# DW08B.net
KiCad netlist of a schematic drawn in EAGLE
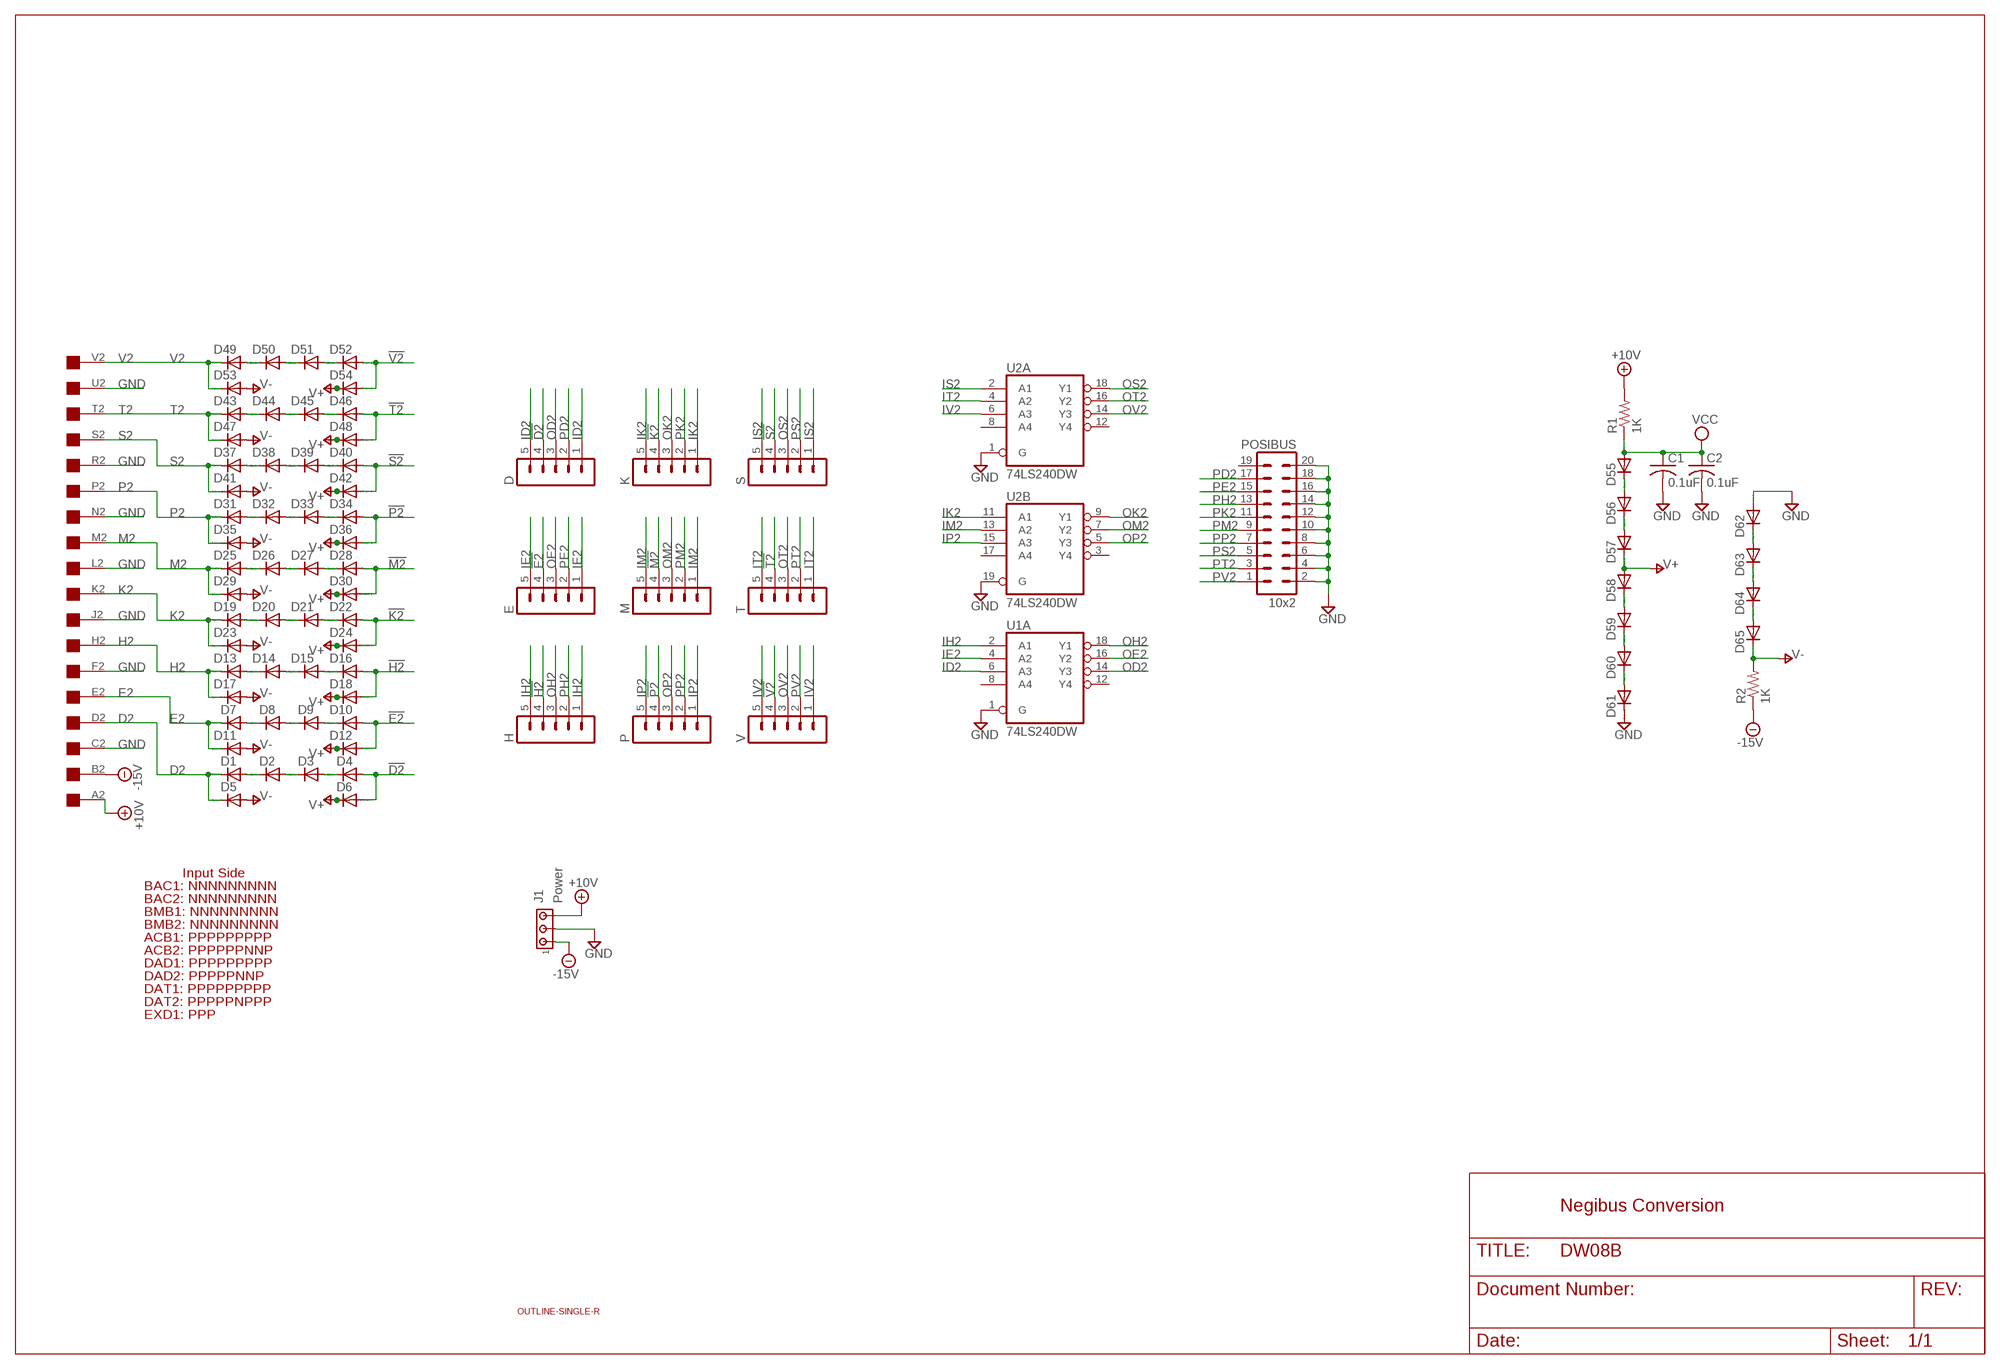
[diagram p0: schematic, sheet 1]

(export (version "E")
  (design (tool "Eeschema 10.0.6"))
  (components
    (comp (ref "C1")
      (value "0.1uF")
      (footprint "eagle-import:C050-025X075")
      (libsource (lib "eagle-import") (part "C-US050-025X075"))
    )
    (comp (ref "C2")
      (value "0.1uF")
      (footprint "eagle-import:C050-025X075")
      (libsource (lib "eagle-import") (part "C-US050-025X075"))
    )
    (comp (ref "D")
      (value "MA05-1")
      (footprint "eagle-import:MA05-1")
      (libsource (lib "eagle-import") (part "MA05-1"))
    )
    (comp (ref "D1")
      (value "1N4148WS")
      (footprint "eagle-import:SOD323-W")
      (libsource (lib "eagle-import") (part "DIODE-SOD323-W"))
    )
    (comp (ref "D2")
      (value "1N4148WS")
      (footprint "eagle-import:SOD323-W")
      (libsource (lib "eagle-import") (part "DIODE-SOD323-W"))
    )
    (comp (ref "D3")
      (value "1N4148WS")
      (footprint "eagle-import:SOD323-W")
      (libsource (lib "eagle-import") (part "DIODE-SOD323-W"))
    )
    (comp (ref "D4")
      (value "1N4148WS")
      (footprint "eagle-import:SOD323-W")
      (libsource (lib "eagle-import") (part "DIODE-SOD323-W"))
    )
    (comp (ref "D5")
      (value "1N4148WS")
      (footprint "eagle-import:SOD323-W")
      (libsource (lib "eagle-import") (part "DIODE-SOD323-W"))
    )
    (comp (ref "D6")
      (value "1N4148WS")
      (footprint "eagle-import:SOD323-W")
      (libsource (lib "eagle-import") (part "DIODE-SOD323-W"))
    )
    (comp (ref "D7")
      (value "1N4148WS")
      (footprint "eagle-import:SOD323-W")
      (libsource (lib "eagle-import") (part "DIODE-SOD323-W"))
    )
    (comp (ref "D8")
      (value "1N4148WS")
      (footprint "eagle-import:SOD323-W")
      (libsource (lib "eagle-import") (part "DIODE-SOD323-W"))
    )
    (comp (ref "D9")
      (value "1N4148WS")
      (footprint "eagle-import:SOD323-W")
      (libsource (lib "eagle-import") (part "DIODE-SOD323-W"))
    )
    (comp (ref "D10")
      (value "1N4148WS")
      (footprint "eagle-import:SOD323-W")
      (libsource (lib "eagle-import") (part "DIODE-SOD323-W"))
    )
    (comp (ref "D11")
      (value "1N4148WS")
      (footprint "eagle-import:SOD323-W")
      (libsource (lib "eagle-import") (part "DIODE-SOD323-W"))
    )
    (comp (ref "D12")
      (value "1N4148WS")
      (footprint "eagle-import:SOD323-W")
      (libsource (lib "eagle-import") (part "DIODE-SOD323-W"))
    )
    (comp (ref "D13")
      (value "1N4148WS")
      (footprint "eagle-import:SOD323-W")
      (libsource (lib "eagle-import") (part "DIODE-SOD323-W"))
    )
    (comp (ref "D14")
      (value "1N4148WS")
      (footprint "eagle-import:SOD323-W")
      (libsource (lib "eagle-import") (part "DIODE-SOD323-W"))
    )
    (comp (ref "D15")
      (value "1N4148WS")
      (footprint "eagle-import:SOD323-W")
      (libsource (lib "eagle-import") (part "DIODE-SOD323-W"))
    )
    (comp (ref "D16")
      (value "1N4148WS")
      (footprint "eagle-import:SOD323-W")
      (libsource (lib "eagle-import") (part "DIODE-SOD323-W"))
    )
    (comp (ref "D17")
      (value "1N4148WS")
      (footprint "eagle-import:SOD323-W")
      (libsource (lib "eagle-import") (part "DIODE-SOD323-W"))
    )
    (comp (ref "D18")
      (value "1N4148WS")
      (footprint "eagle-import:SOD323-W")
      (libsource (lib "eagle-import") (part "DIODE-SOD323-W"))
    )
    (comp (ref "D19")
      (value "1N4148WS")
      (footprint "eagle-import:SOD323-W")
      (libsource (lib "eagle-import") (part "DIODE-SOD323-W"))
    )
    (comp (ref "D20")
      (value "1N4148WS")
      (footprint "eagle-import:SOD323-W")
      (libsource (lib "eagle-import") (part "DIODE-SOD323-W"))
    )
    (comp (ref "D21")
      (value "1N4148WS")
      (footprint "eagle-import:SOD323-W")
      (libsource (lib "eagle-import") (part "DIODE-SOD323-W"))
    )
    (comp (ref "D22")
      (value "1N4148WS")
      (footprint "eagle-import:SOD323-W")
      (libsource (lib "eagle-import") (part "DIODE-SOD323-W"))
    )
    (comp (ref "D23")
      (value "1N4148WS")
      (footprint "eagle-import:SOD323-W")
      (libsource (lib "eagle-import") (part "DIODE-SOD323-W"))
    )
    (comp (ref "D24")
      (value "1N4148WS")
      (footprint "eagle-import:SOD323-W")
      (libsource (lib "eagle-import") (part "DIODE-SOD323-W"))
    )
    (comp (ref "D25")
      (value "1N4148WS")
      (footprint "eagle-import:SOD323-W")
      (libsource (lib "eagle-import") (part "DIODE-SOD323-W"))
    )
    (comp (ref "D26")
      (value "1N4148WS")
      (footprint "eagle-import:SOD323-W")
      (libsource (lib "eagle-import") (part "DIODE-SOD323-W"))
    )
    (comp (ref "D27")
      (value "1N4148WS")
      (footprint "eagle-import:SOD323-W")
      (libsource (lib "eagle-import") (part "DIODE-SOD323-W"))
    )
    (comp (ref "D28")
      (value "1N4148WS")
      (footprint "eagle-import:SOD323-W")
      (libsource (lib "eagle-import") (part "DIODE-SOD323-W"))
    )
    (comp (ref "D29")
      (value "1N4148WS")
      (footprint "eagle-import:SOD323-W")
      (libsource (lib "eagle-import") (part "DIODE-SOD323-W"))
    )
    (comp (ref "D30")
      (value "1N4148WS")
      (footprint "eagle-import:SOD323-W")
      (libsource (lib "eagle-import") (part "DIODE-SOD323-W"))
    )
    (comp (ref "D31")
      (value "1N4148WS")
      (footprint "eagle-import:SOD323-W")
      (libsource (lib "eagle-import") (part "DIODE-SOD323-W"))
    )
    (comp (ref "D32")
      (value "1N4148WS")
      (footprint "eagle-import:SOD323-W")
      (libsource (lib "eagle-import") (part "DIODE-SOD323-W"))
    )
    (comp (ref "D33")
      (value "1N4148WS")
      (footprint "eagle-import:SOD323-W")
      (libsource (lib "eagle-import") (part "DIODE-SOD323-W"))
    )
    (comp (ref "D34")
      (value "1N4148WS")
      (footprint "eagle-import:SOD323-W")
      (libsource (lib "eagle-import") (part "DIODE-SOD323-W"))
    )
    (comp (ref "D35")
      (value "1N4148WS")
      (footprint "eagle-import:SOD323-W")
      (libsource (lib "eagle-import") (part "DIODE-SOD323-W"))
    )
    (comp (ref "D36")
      (value "1N4148WS")
      (footprint "eagle-import:SOD323-W")
      (libsource (lib "eagle-import") (part "DIODE-SOD323-W"))
    )
    (comp (ref "D37")
      (value "1N4148WS")
      (footprint "eagle-import:SOD323-W")
      (libsource (lib "eagle-import") (part "DIODE-SOD323-W"))
    )
    (comp (ref "D38")
      (value "1N4148WS")
      (footprint "eagle-import:SOD323-W")
      (libsource (lib "eagle-import") (part "DIODE-SOD323-W"))
    )
    (comp (ref "D39")
      (value "1N4148WS")
      (footprint "eagle-import:SOD323-W")
      (libsource (lib "eagle-import") (part "DIODE-SOD323-W"))
    )
    (comp (ref "D40")
      (value "1N4148WS")
      (footprint "eagle-import:SOD323-W")
      (libsource (lib "eagle-import") (part "DIODE-SOD323-W"))
    )
    (comp (ref "D41")
      (value "1N4148WS")
      (footprint "eagle-import:SOD323-W")
      (libsource (lib "eagle-import") (part "DIODE-SOD323-W"))
    )
    (comp (ref "D42")
      (value "1N4148WS")
      (footprint "eagle-import:SOD323-W")
      (libsource (lib "eagle-import") (part "DIODE-SOD323-W"))
    )
    (comp (ref "D43")
      (value "1N4148WS")
      (footprint "eagle-import:SOD323-W")
      (libsource (lib "eagle-import") (part "DIODE-SOD323-W"))
    )
    (comp (ref "D44")
      (value "1N4148WS")
      (footprint "eagle-import:SOD323-W")
      (libsource (lib "eagle-import") (part "DIODE-SOD323-W"))
    )
    (comp (ref "D45")
      (value "1N4148WS")
      (footprint "eagle-import:SOD323-W")
      (libsource (lib "eagle-import") (part "DIODE-SOD323-W"))
    )
    (comp (ref "D46")
      (value "1N4148WS")
      (footprint "eagle-import:SOD323-W")
      (libsource (lib "eagle-import") (part "DIODE-SOD323-W"))
    )
    (comp (ref "D47")
      (value "1N4148WS")
      (footprint "eagle-import:SOD323-W")
      (libsource (lib "eagle-import") (part "DIODE-SOD323-W"))
    )
    (comp (ref "D48")
      (value "1N4148WS")
      (footprint "eagle-import:SOD323-W")
      (libsource (lib "eagle-import") (part "DIODE-SOD323-W"))
    )
    (comp (ref "D49")
      (value "1N4148WS")
      (footprint "eagle-import:SOD323-W")
      (libsource (lib "eagle-import") (part "DIODE-SOD323-W"))
    )
    (comp (ref "D50")
      (value "1N4148WS")
      (footprint "eagle-import:SOD323-W")
      (libsource (lib "eagle-import") (part "DIODE-SOD323-W"))
    )
    (comp (ref "D51")
      (value "1N4148WS")
      (footprint "eagle-import:SOD323-W")
      (libsource (lib "eagle-import") (part "DIODE-SOD323-W"))
    )
    (comp (ref "D52")
      (value "1N4148WS")
      (footprint "eagle-import:SOD323-W")
      (libsource (lib "eagle-import") (part "DIODE-SOD323-W"))
    )
    (comp (ref "D53")
      (value "1N4148WS")
      (footprint "eagle-import:SOD323-W")
      (libsource (lib "eagle-import") (part "DIODE-SOD323-W"))
    )
    (comp (ref "D54")
      (value "1N4148WS")
      (footprint "eagle-import:SOD323-W")
      (libsource (lib "eagle-import") (part "DIODE-SOD323-W"))
    )
    (comp (ref "D55")
      (value "1N4148WS")
      (footprint "eagle-import:SOD323-W")
      (libsource (lib "eagle-import") (part "DIODE-SOD323-W"))
    )
    (comp (ref "D56")
      (value "1N4148WS")
      (footprint "eagle-import:SOD323-W")
      (libsource (lib "eagle-import") (part "DIODE-SOD323-W"))
    )
    (comp (ref "D57")
      (value "1N4148WS")
      (footprint "eagle-import:SOD323-W")
      (libsource (lib "eagle-import") (part "DIODE-SOD323-W"))
    )
    (comp (ref "D58")
      (value "1N4148WS")
      (footprint "eagle-import:SOD323-W")
      (libsource (lib "eagle-import") (part "DIODE-SOD323-W"))
    )
    (comp (ref "D59")
      (value "1N4148WS")
      (footprint "eagle-import:SOD323-W")
      (libsource (lib "eagle-import") (part "DIODE-SOD323-W"))
    )
    (comp (ref "D60")
      (value "1N4148WS")
      (footprint "eagle-import:SOD323-W")
      (libsource (lib "eagle-import") (part "DIODE-SOD323-W"))
    )
    (comp (ref "D61")
      (value "1N4148WS")
      (footprint "eagle-import:SOD323-W")
      (libsource (lib "eagle-import") (part "DIODE-SOD323-W"))
    )
    (comp (ref "D62")
      (value "1N4148WS")
      (footprint "eagle-import:SOD323-W")
      (libsource (lib "eagle-import") (part "DIODE-SOD323-W"))
    )
    (comp (ref "D63")
      (value "1N4148WS")
      (footprint "eagle-import:SOD323-W")
      (libsource (lib "eagle-import") (part "DIODE-SOD323-W"))
    )
    (comp (ref "D64")
      (value "1N4148WS")
      (footprint "eagle-import:SOD323-W")
      (libsource (lib "eagle-import") (part "DIODE-SOD323-W"))
    )
    (comp (ref "D65")
      (value "1N4148WS")
      (footprint "eagle-import:SOD323-W")
      (libsource (lib "eagle-import") (part "DIODE-SOD323-W"))
    )
    (comp (ref "E")
      (value "MA05-1")
      (footprint "eagle-import:MA05-1")
      (libsource (lib "eagle-import") (part "MA05-1"))
    )
    (comp (ref "H")
      (value "MA05-1")
      (footprint "eagle-import:MA05-1")
      (libsource (lib "eagle-import") (part "MA05-1"))
    )
    (comp (ref "J1")
      (value "Power")
      (footprint "eagle-import:10X03MTA")
      (libsource (lib "eagle-import") (part "MTA03-100"))
    )
    (comp (ref "K")
      (value "MA05-1")
      (footprint "eagle-import:MA05-1")
      (libsource (lib "eagle-import") (part "MA05-1"))
    )
    (comp (ref "M")
      (value "MA05-1")
      (footprint "eagle-import:MA05-1")
      (libsource (lib "eagle-import") (part "MA05-1"))
    )
    (comp (ref "P")
      (value "MA05-1")
      (footprint "eagle-import:MA05-1")
      (libsource (lib "eagle-import") (part "MA05-1"))
    )
    (comp (ref "POSIBUS")
      (value "10x2")
      (footprint "eagle-import:MA10-2")
      (libsource (lib "eagle-import") (part "MA10-2"))
    )
    (comp (ref "R1")
      (value "1K")
      (footprint "eagle-import:0207_10")
      (libsource (lib "eagle-import") (part "R-US_0207/10"))
    )
    (comp (ref "R2")
      (value "1K")
      (footprint "eagle-import:0207_10")
      (libsource (lib "eagle-import") (part "R-US_0207/10"))
    )
    (comp (ref "S")
      (value "MA05-1")
      (footprint "eagle-import:MA05-1")
      (libsource (lib "eagle-import") (part "MA05-1"))
    )
    (comp (ref "T")
      (value "MA05-1")
      (footprint "eagle-import:MA05-1")
      (libsource (lib "eagle-import") (part "MA05-1"))
    )
    (comp (ref "U$1")
      (value "OUTLINE-SINGLE-R")
      (footprint "eagle-import:SINGLE-R")
      (libsource (lib "eagle-import") (part "OUTLINE-SINGLE-R"))
    )
    (comp (ref "U$2")
      (value "EDGE")
      (footprint "eagle-import:EDGE-CON2")
      (libsource (lib "eagle-import") (part "SINGLE"))
    )
    (comp (ref "U1")
      (value "74LS240DW")
      (footprint "eagle-import:SO20W")
      (libsource (lib "eagle-import") (part "74240DWLS"))
    )
    (comp (ref "U2")
      (value "74LS240DW")
      (footprint "eagle-import:SO20W")
      (libsource (lib "eagle-import") (part "74240DWLS"))
    )
    (comp (ref "V")
      (value "MA05-1")
      (footprint "eagle-import:MA05-1")
      (libsource (lib "eagle-import") (part "MA05-1"))
    )
  )
  (nets
    (net (code "1") (name "+10V") (class "Default")
      (node (ref "J1") (pin "3") (pinfunction "3_3") (pintype "passive"))
      (node (ref "R1") (pin "2") (pinfunction "2_2") (pintype "passive"))
      (node (ref "U$2") (pin "A2") (pinfunction "1_A2") (pintype "bidirectional"))
    )
    (net (code "2") (name "-15V") (class "Default")
      (node (ref "J1") (pin "1") (pinfunction "1_1") (pintype "passive"))
      (node (ref "R2") (pin "1") (pinfunction "1_1") (pintype "passive"))
      (node (ref "U$2") (pin "B2") (pinfunction "1_B2") (pintype "bidirectional"))
    )
    (net (code "3") (name "/D2") (class "Default")
      (node (ref "D1") (pin "C") (pinfunction "C_C") (pintype "passive"))
      (node (ref "D5") (pin "C") (pinfunction "C_C") (pintype "passive"))
      (node (ref "U$2") (pin "D2") (pinfunction "1_D2") (pintype "bidirectional"))
    )
    (net (code "4") (name "/E2") (class "Default")
      (node (ref "D11") (pin "C") (pinfunction "C_C") (pintype "passive"))
      (node (ref "D7") (pin "C") (pinfunction "C_C") (pintype "passive"))
      (node (ref "U$2") (pin "E2") (pinfunction "1_E2") (pintype "bidirectional"))
    )
    (net (code "5") (name "/H2") (class "Default")
      (node (ref "D13") (pin "C") (pinfunction "C_C") (pintype "passive"))
      (node (ref "D17") (pin "C") (pinfunction "C_C") (pintype "passive"))
      (node (ref "U$2") (pin "H2") (pinfunction "1_H2") (pintype "bidirectional"))
    )
    (net (code "6") (name "/ID2") (class "Default")
      (node (ref "D") (pin "1") (pinfunction "1_1") (pintype "passive"))
      (node (ref "D") (pin "5") (pinfunction "5_5") (pintype "passive"))
      (node (ref "U1") (pin "6") (pinfunction "A3_6") (pintype "input"))
    )
    (net (code "7") (name "/IE2") (class "Default")
      (node (ref "E") (pin "1") (pinfunction "1_1") (pintype "passive"))
      (node (ref "E") (pin "5") (pinfunction "5_5") (pintype "passive"))
      (node (ref "U1") (pin "4") (pinfunction "A2_4") (pintype "input"))
    )
    (net (code "8") (name "/IH2") (class "Default")
      (node (ref "H") (pin "1") (pinfunction "1_1") (pintype "passive"))
      (node (ref "H") (pin "5") (pinfunction "5_5") (pintype "passive"))
      (node (ref "U1") (pin "2") (pinfunction "A1_2") (pintype "input"))
    )
    (net (code "9") (name "/IK2") (class "Default")
      (node (ref "K") (pin "1") (pinfunction "1_1") (pintype "passive"))
      (node (ref "K") (pin "5") (pinfunction "5_5") (pintype "passive"))
      (node (ref "U2") (pin "11") (pinfunction "A1_11") (pintype "input"))
    )
    (net (code "10") (name "/IM2") (class "Default")
      (node (ref "M") (pin "1") (pinfunction "1_1") (pintype "passive"))
      (node (ref "M") (pin "5") (pinfunction "5_5") (pintype "passive"))
      (node (ref "U2") (pin "13") (pinfunction "A2_13") (pintype "input"))
    )
    (net (code "11") (name "/IP2") (class "Default")
      (node (ref "P") (pin "1") (pinfunction "1_1") (pintype "passive"))
      (node (ref "P") (pin "5") (pinfunction "5_5") (pintype "passive"))
      (node (ref "U2") (pin "15") (pinfunction "A3_15") (pintype "input"))
    )
    (net (code "12") (name "/IS2") (class "Default")
      (node (ref "S") (pin "1") (pinfunction "1_1") (pintype "passive"))
      (node (ref "S") (pin "5") (pinfunction "5_5") (pintype "passive"))
      (node (ref "U2") (pin "2") (pinfunction "A1_2") (pintype "input"))
    )
    (net (code "13") (name "/IT2") (class "Default")
      (node (ref "T") (pin "1") (pinfunction "1_1") (pintype "passive"))
      (node (ref "T") (pin "5") (pinfunction "5_5") (pintype "passive"))
      (node (ref "U2") (pin "4") (pinfunction "A2_4") (pintype "input"))
    )
    (net (code "14") (name "/IV2") (class "Default")
      (node (ref "U2") (pin "6") (pinfunction "A3_6") (pintype "input"))
      (node (ref "V") (pin "1") (pinfunction "1_1") (pintype "passive"))
      (node (ref "V") (pin "5") (pinfunction "5_5") (pintype "passive"))
    )
    (net (code "15") (name "/K2") (class "Default")
      (node (ref "D19") (pin "C") (pinfunction "C_C") (pintype "passive"))
      (node (ref "D23") (pin "C") (pinfunction "C_C") (pintype "passive"))
      (node (ref "U$2") (pin "K2") (pinfunction "1_K2") (pintype "bidirectional"))
    )
    (net (code "16") (name "/M2") (class "Default")
      (node (ref "D25") (pin "C") (pinfunction "C_C") (pintype "passive"))
      (node (ref "D29") (pin "C") (pinfunction "C_C") (pintype "passive"))
      (node (ref "U$2") (pin "M2") (pinfunction "1_M2") (pintype "bidirectional"))
    )
    (net (code "17") (name "/OD2") (class "Default")
      (node (ref "D") (pin "3") (pinfunction "3_3") (pintype "passive"))
      (node (ref "U1") (pin "14") (pinfunction "Y3_14") (pintype "tri_state"))
    )
    (net (code "18") (name "/OE2") (class "Default")
      (node (ref "E") (pin "3") (pinfunction "3_3") (pintype "passive"))
      (node (ref "U1") (pin "16") (pinfunction "Y2_16") (pintype "tri_state"))
    )
    (net (code "19") (name "/OH2") (class "Default")
      (node (ref "H") (pin "3") (pinfunction "3_3") (pintype "passive"))
      (node (ref "U1") (pin "18") (pinfunction "Y1_18") (pintype "tri_state"))
    )
    (net (code "20") (name "/OK2") (class "Default")
      (node (ref "K") (pin "3") (pinfunction "3_3") (pintype "passive"))
      (node (ref "U2") (pin "9") (pinfunction "Y1_9") (pintype "tri_state"))
    )
    (net (code "21") (name "/OM2") (class "Default")
      (node (ref "M") (pin "3") (pinfunction "3_3") (pintype "passive"))
      (node (ref "U2") (pin "7") (pinfunction "Y2_7") (pintype "tri_state"))
    )
    (net (code "22") (name "/OP2") (class "Default")
      (node (ref "P") (pin "3") (pinfunction "3_3") (pintype "passive"))
      (node (ref "U2") (pin "5") (pinfunction "Y3_5") (pintype "tri_state"))
    )
    (net (code "23") (name "/OS2") (class "Default")
      (node (ref "S") (pin "3") (pinfunction "3_3") (pintype "passive"))
      (node (ref "U2") (pin "18") (pinfunction "Y1_18") (pintype "tri_state"))
    )
    (net (code "24") (name "/OT2") (class "Default")
      (node (ref "T") (pin "3") (pinfunction "3_3") (pintype "passive"))
      (node (ref "U2") (pin "16") (pinfunction "Y2_16") (pintype "tri_state"))
    )
    (net (code "25") (name "/OV2") (class "Default")
      (node (ref "U2") (pin "14") (pinfunction "Y3_14") (pintype "tri_state"))
      (node (ref "V") (pin "3") (pinfunction "3_3") (pintype "passive"))
    )
    (net (code "26") (name "/P2") (class "Default")
      (node (ref "D31") (pin "C") (pinfunction "C_C") (pintype "passive"))
      (node (ref "D35") (pin "C") (pinfunction "C_C") (pintype "passive"))
      (node (ref "U$2") (pin "P2") (pinfunction "1_P2") (pintype "bidirectional"))
    )
    (net (code "27") (name "/PD2") (class "Default")
      (node (ref "D") (pin "2") (pinfunction "2_2") (pintype "passive"))
      (node (ref "POSIBUS") (pin "17") (pinfunction "17_17") (pintype "passive"))
    )
    (net (code "28") (name "/PE2") (class "Default")
      (node (ref "E") (pin "2") (pinfunction "2_2") (pintype "passive"))
      (node (ref "POSIBUS") (pin "15") (pinfunction "15_15") (pintype "passive"))
    )
    (net (code "29") (name "/PH2") (class "Default")
      (node (ref "H") (pin "2") (pinfunction "2_2") (pintype "passive"))
      (node (ref "POSIBUS") (pin "13") (pinfunction "13_13") (pintype "passive"))
    )
    (net (code "30") (name "/PK2") (class "Default")
      (node (ref "K") (pin "2") (pinfunction "2_2") (pintype "passive"))
      (node (ref "POSIBUS") (pin "11") (pinfunction "11_11") (pintype "passive"))
    )
    (net (code "31") (name "/PM2") (class "Default")
      (node (ref "M") (pin "2") (pinfunction "2_2") (pintype "passive"))
      (node (ref "POSIBUS") (pin "9") (pinfunction "9_9") (pintype "passive"))
    )
    (net (code "32") (name "/PP2") (class "Default")
      (node (ref "P") (pin "2") (pinfunction "2_2") (pintype "passive"))
      (node (ref "POSIBUS") (pin "7") (pinfunction "7_7") (pintype "passive"))
    )
    (net (code "33") (name "/PS2") (class "Default")
      (node (ref "POSIBUS") (pin "5") (pinfunction "5_5") (pintype "passive"))
      (node (ref "S") (pin "2") (pinfunction "2_2") (pintype "passive"))
    )
    (net (code "34") (name "/PT2") (class "Default")
      (node (ref "POSIBUS") (pin "3") (pinfunction "3_3") (pintype "passive"))
      (node (ref "T") (pin "2") (pinfunction "2_2") (pintype "passive"))
    )
    (net (code "35") (name "/PV2") (class "Default")
      (node (ref "POSIBUS") (pin "1") (pinfunction "1_1") (pintype "passive"))
      (node (ref "V") (pin "2") (pinfunction "2_2") (pintype "passive"))
    )
    (net (code "36") (name "/S2") (class "Default")
      (node (ref "D37") (pin "C") (pinfunction "C_C") (pintype "passive"))
      (node (ref "D41") (pin "C") (pinfunction "C_C") (pintype "passive"))
      (node (ref "U$2") (pin "S2") (pinfunction "1_S2") (pintype "bidirectional"))
    )
    (net (code "37") (name "/T2") (class "Default")
      (node (ref "D43") (pin "C") (pinfunction "C_C") (pintype "passive"))
      (node (ref "D47") (pin "C") (pinfunction "C_C") (pintype "passive"))
      (node (ref "U$2") (pin "T2") (pinfunction "1_T2") (pintype "bidirectional"))
    )
    (net (code "38") (name "/V2") (class "Default")
      (node (ref "D49") (pin "C") (pinfunction "C_C") (pintype "passive"))
      (node (ref "D53") (pin "C") (pinfunction "C_C") (pintype "passive"))
      (node (ref "U$2") (pin "V2") (pinfunction "1_V2") (pintype "bidirectional"))
    )
    (net (code "39") (name "/~{D2}") (class "Default")
      (node (ref "D") (pin "4") (pinfunction "4_4") (pintype "passive"))
      (node (ref "D4") (pin "A") (pinfunction "A_A") (pintype "passive"))
      (node (ref "D6") (pin "A") (pinfunction "A_A") (pintype "passive"))
    )
    (net (code "40") (name "/~{E2}") (class "Default")
      (node (ref "D10") (pin "A") (pinfunction "A_A") (pintype "passive"))
      (node (ref "D12") (pin "A") (pinfunction "A_A") (pintype "passive"))
      (node (ref "E") (pin "4") (pinfunction "4_4") (pintype "passive"))
    )
    (net (code "41") (name "/~{H2}") (class "Default")
      (node (ref "D16") (pin "A") (pinfunction "A_A") (pintype "passive"))
      (node (ref "D18") (pin "A") (pinfunction "A_A") (pintype "passive"))
      (node (ref "H") (pin "4") (pinfunction "4_4") (pintype "passive"))
    )
    (net (code "42") (name "/~{K2}") (class "Default")
      (node (ref "D22") (pin "A") (pinfunction "A_A") (pintype "passive"))
      (node (ref "D24") (pin "A") (pinfunction "A_A") (pintype "passive"))
      (node (ref "K") (pin "4") (pinfunction "4_4") (pintype "passive"))
    )
    (net (code "43") (name "/~{M2}") (class "Default")
      (node (ref "D28") (pin "A") (pinfunction "A_A") (pintype "passive"))
      (node (ref "D30") (pin "A") (pinfunction "A_A") (pintype "passive"))
      (node (ref "M") (pin "4") (pinfunction "4_4") (pintype "passive"))
    )
    (net (code "44") (name "/~{P2}") (class "Default")
      (node (ref "D34") (pin "A") (pinfunction "A_A") (pintype "passive"))
      (node (ref "D36") (pin "A") (pinfunction "A_A") (pintype "passive"))
      (node (ref "P") (pin "4") (pinfunction "4_4") (pintype "passive"))
    )
    (net (code "45") (name "/~{S2}") (class "Default")
      (node (ref "D40") (pin "A") (pinfunction "A_A") (pintype "passive"))
      (node (ref "D42") (pin "A") (pinfunction "A_A") (pintype "passive"))
      (node (ref "S") (pin "4") (pinfunction "4_4") (pintype "passive"))
    )
    (net (code "46") (name "/~{T2}") (class "Default")
      (node (ref "D46") (pin "A") (pinfunction "A_A") (pintype "passive"))
      (node (ref "D48") (pin "A") (pinfunction "A_A") (pintype "passive"))
      (node (ref "T") (pin "4") (pinfunction "4_4") (pintype "passive"))
    )
    (net (code "47") (name "/~{V2}") (class "Default")
      (node (ref "D52") (pin "A") (pinfunction "A_A") (pintype "passive"))
      (node (ref "D54") (pin "A") (pinfunction "A_A") (pintype "passive"))
      (node (ref "V") (pin "4") (pinfunction "4_4") (pintype "passive"))
    )
    (net (code "48") (name "GND") (class "Default")
      (node (ref "C1") (pin "2") (pinfunction "2_2") (pintype "passive"))
      (node (ref "C2") (pin "2") (pinfunction "2_2") (pintype "passive"))
      (node (ref "D61") (pin "C") (pinfunction "C_C") (pintype "passive"))
      (node (ref "D62") (pin "A") (pinfunction "A_A") (pintype "passive"))
      (node (ref "J1") (pin "2") (pinfunction "2_2") (pintype "passive"))
      (node (ref "POSIBUS") (pin "10") (pinfunction "10_10") (pintype "passive"))
      (node (ref "POSIBUS") (pin "12") (pinfunction "12_12") (pintype "passive"))
      (node (ref "POSIBUS") (pin "14") (pinfunction "14_14") (pintype "passive"))
      (node (ref "POSIBUS") (pin "16") (pinfunction "16_16") (pintype "passive"))
      (node (ref "POSIBUS") (pin "18") (pinfunction "18_18") (pintype "passive"))
      (node (ref "POSIBUS") (pin "2") (pinfunction "2_2") (pintype "passive"))
      (node (ref "POSIBUS") (pin "20") (pinfunction "20_20") (pintype "passive"))
      (node (ref "POSIBUS") (pin "4") (pinfunction "4_4") (pintype "passive"))
      (node (ref "POSIBUS") (pin "6") (pinfunction "6_6") (pintype "passive"))
      (node (ref "POSIBUS") (pin "8") (pinfunction "8_8") (pintype "passive"))
      (node (ref "U$2") (pin "C2") (pinfunction "1_C2") (pintype "bidirectional"))
      (node (ref "U$2") (pin "F2") (pinfunction "1_F2") (pintype "bidirectional"))
      (node (ref "U$2") (pin "J2") (pinfunction "1_J2") (pintype "bidirectional"))
      (node (ref "U$2") (pin "L2") (pinfunction "1_L2") (pintype "bidirectional"))
      (node (ref "U$2") (pin "N2") (pinfunction "1_N2") (pintype "bidirectional"))
      (node (ref "U$2") (pin "R2") (pinfunction "1_R2") (pintype "bidirectional"))
      (node (ref "U$2") (pin "U2") (pinfunction "1_U2") (pintype "bidirectional"))
      (node (ref "U1") (pin "1") (pinfunction "G_1") (pintype "input"))
      (node (ref "U2") (pin "1") (pinfunction "G_1") (pintype "input"))
      (node (ref "U2") (pin "19") (pinfunction "G_19") (pintype "input"))
    )
    (net (code "49") (name "Net-(D1-PadA)") (class "Default")
      (node (ref "D1") (pin "A") (pinfunction "A_A") (pintype "passive"))
      (node (ref "D2") (pin "C") (pinfunction "C_C") (pintype "passive"))
    )
    (net (code "50") (name "Net-(D2-PadA)") (class "Default")
      (node (ref "D2") (pin "A") (pinfunction "A_A") (pintype "passive"))
      (node (ref "D3") (pin "C") (pinfunction "C_C") (pintype "passive"))
    )
    (net (code "51") (name "Net-(D3-PadA)") (class "Default")
      (node (ref "D3") (pin "A") (pinfunction "A_A") (pintype "passive"))
      (node (ref "D4") (pin "C") (pinfunction "C_C") (pintype "passive"))
    )
    (net (code "52") (name "Net-(D7-PadA)") (class "Default")
      (node (ref "D7") (pin "A") (pinfunction "A_A") (pintype "passive"))
      (node (ref "D8") (pin "C") (pinfunction "C_C") (pintype "passive"))
    )
    (net (code "53") (name "Net-(D8-PadA)") (class "Default")
      (node (ref "D8") (pin "A") (pinfunction "A_A") (pintype "passive"))
      (node (ref "D9") (pin "C") (pinfunction "C_C") (pintype "passive"))
    )
    (net (code "54") (name "Net-(D10-PadC)") (class "Default")
      (node (ref "D10") (pin "C") (pinfunction "C_C") (pintype "passive"))
      (node (ref "D9") (pin "A") (pinfunction "A_A") (pintype "passive"))
    )
    (net (code "55") (name "Net-(D13-PadA)") (class "Default")
      (node (ref "D13") (pin "A") (pinfunction "A_A") (pintype "passive"))
      (node (ref "D14") (pin "C") (pinfunction "C_C") (pintype "passive"))
    )
    (net (code "56") (name "Net-(D14-PadA)") (class "Default")
      (node (ref "D14") (pin "A") (pinfunction "A_A") (pintype "passive"))
      (node (ref "D15") (pin "C") (pinfunction "C_C") (pintype "passive"))
    )
    (net (code "57") (name "Net-(D15-PadA)") (class "Default")
      (node (ref "D15") (pin "A") (pinfunction "A_A") (pintype "passive"))
      (node (ref "D16") (pin "C") (pinfunction "C_C") (pintype "passive"))
    )
    (net (code "58") (name "Net-(D19-PadA)") (class "Default")
      (node (ref "D19") (pin "A") (pinfunction "A_A") (pintype "passive"))
      (node (ref "D20") (pin "C") (pinfunction "C_C") (pintype "passive"))
    )
    (net (code "59") (name "Net-(D20-PadA)") (class "Default")
      (node (ref "D20") (pin "A") (pinfunction "A_A") (pintype "passive"))
      (node (ref "D21") (pin "C") (pinfunction "C_C") (pintype "passive"))
    )
    (net (code "60") (name "Net-(D21-PadA)") (class "Default")
      (node (ref "D21") (pin "A") (pinfunction "A_A") (pintype "passive"))
      (node (ref "D22") (pin "C") (pinfunction "C_C") (pintype "passive"))
    )
    (net (code "61") (name "Net-(D25-PadA)") (class "Default")
      (node (ref "D25") (pin "A") (pinfunction "A_A") (pintype "passive"))
      (node (ref "D26") (pin "C") (pinfunction "C_C") (pintype "passive"))
    )
    (net (code "62") (name "Net-(D26-PadA)") (class "Default")
      (node (ref "D26") (pin "A") (pinfunction "A_A") (pintype "passive"))
      (node (ref "D27") (pin "C") (pinfunction "C_C") (pintype "passive"))
    )
    (net (code "63") (name "Net-(D27-PadA)") (class "Default")
      (node (ref "D27") (pin "A") (pinfunction "A_A") (pintype "passive"))
      (node (ref "D28") (pin "C") (pinfunction "C_C") (pintype "passive"))
    )
    (net (code "64") (name "Net-(D31-PadA)") (class "Default")
      (node (ref "D31") (pin "A") (pinfunction "A_A") (pintype "passive"))
      (node (ref "D32") (pin "C") (pinfunction "C_C") (pintype "passive"))
    )
    (net (code "65") (name "Net-(D32-PadA)") (class "Default")
      (node (ref "D32") (pin "A") (pinfunction "A_A") (pintype "passive"))
      (node (ref "D33") (pin "C") (pinfunction "C_C") (pintype "passive"))
    )
    (net (code "66") (name "Net-(D33-PadA)") (class "Default")
      (node (ref "D33") (pin "A") (pinfunction "A_A") (pintype "passive"))
      (node (ref "D34") (pin "C") (pinfunction "C_C") (pintype "passive"))
    )
    (net (code "67") (name "Net-(D37-PadA)") (class "Default")
      (node (ref "D37") (pin "A") (pinfunction "A_A") (pintype "passive"))
      (node (ref "D38") (pin "C") (pinfunction "C_C") (pintype "passive"))
    )
    (net (code "68") (name "Net-(D38-PadA)") (class "Default")
      (node (ref "D38") (pin "A") (pinfunction "A_A") (pintype "passive"))
      (node (ref "D39") (pin "C") (pinfunction "C_C") (pintype "passive"))
    )
    (net (code "69") (name "Net-(D39-PadA)") (class "Default")
      (node (ref "D39") (pin "A") (pinfunction "A_A") (pintype "passive"))
      (node (ref "D40") (pin "C") (pinfunction "C_C") (pintype "passive"))
    )
    (net (code "70") (name "Net-(D43-PadA)") (class "Default")
      (node (ref "D43") (pin "A") (pinfunction "A_A") (pintype "passive"))
      (node (ref "D44") (pin "C") (pinfunction "C_C") (pintype "passive"))
    )
    (net (code "71") (name "Net-(D44-PadA)") (class "Default")
      (node (ref "D44") (pin "A") (pinfunction "A_A") (pintype "passive"))
      (node (ref "D45") (pin "C") (pinfunction "C_C") (pintype "passive"))
    )
    (net (code "72") (name "Net-(D45-PadA)") (class "Default")
      (node (ref "D45") (pin "A") (pinfunction "A_A") (pintype "passive"))
      (node (ref "D46") (pin "C") (pinfunction "C_C") (pintype "passive"))
    )
    (net (code "73") (name "Net-(D49-PadA)") (class "Default")
      (node (ref "D49") (pin "A") (pinfunction "A_A") (pintype "passive"))
      (node (ref "D50") (pin "C") (pinfunction "C_C") (pintype "passive"))
    )
    (net (code "74") (name "Net-(D50-PadA)") (class "Default")
      (node (ref "D50") (pin "A") (pinfunction "A_A") (pintype "passive"))
      (node (ref "D51") (pin "C") (pinfunction "C_C") (pintype "passive"))
    )
    (net (code "75") (name "Net-(D51-PadA)") (class "Default")
      (node (ref "D51") (pin "A") (pinfunction "A_A") (pintype "passive"))
      (node (ref "D52") (pin "C") (pinfunction "C_C") (pintype "passive"))
    )
    (net (code "76") (name "Net-(D55-PadC)") (class "Default")
      (node (ref "D55") (pin "C") (pinfunction "C_C") (pintype "passive"))
      (node (ref "D56") (pin "A") (pinfunction "A_A") (pintype "passive"))
    )
    (net (code "77") (name "Net-(D56-PadC)") (class "Default")
      (node (ref "D56") (pin "C") (pinfunction "C_C") (pintype "passive"))
      (node (ref "D57") (pin "A") (pinfunction "A_A") (pintype "passive"))
    )
    (net (code "78") (name "Net-(D58-PadC)") (class "Default")
      (node (ref "D58") (pin "C") (pinfunction "C_C") (pintype "passive"))
      (node (ref "D59") (pin "A") (pinfunction "A_A") (pintype "passive"))
    )
    (net (code "79") (name "Net-(D59-PadC)") (class "Default")
      (node (ref "D59") (pin "C") (pinfunction "C_C") (pintype "passive"))
      (node (ref "D60") (pin "A") (pinfunction "A_A") (pintype "passive"))
    )
    (net (code "80") (name "Net-(D60-PadC)") (class "Default")
      (node (ref "D60") (pin "C") (pinfunction "C_C") (pintype "passive"))
      (node (ref "D61") (pin "A") (pinfunction "A_A") (pintype "passive"))
    )
    (net (code "81") (name "Net-(D62-PadC)") (class "Default")
      (node (ref "D62") (pin "C") (pinfunction "C_C") (pintype "passive"))
      (node (ref "D63") (pin "A") (pinfunction "A_A") (pintype "passive"))
    )
    (net (code "82") (name "Net-(D63-PadC)") (class "Default")
      (node (ref "D63") (pin "C") (pinfunction "C_C") (pintype "passive"))
      (node (ref "D64") (pin "A") (pinfunction "A_A") (pintype "passive"))
    )
    (net (code "83") (name "Net-(D64-PadC)") (class "Default")
      (node (ref "D64") (pin "C") (pinfunction "C_C") (pintype "passive"))
      (node (ref "D65") (pin "A") (pinfunction "A_A") (pintype "passive"))
    )
    (net (code "84") (name "V+") (class "Default")
      (node (ref "D12") (pin "C") (pinfunction "C_C") (pintype "passive"))
      (node (ref "D18") (pin "C") (pinfunction "C_C") (pintype "passive"))
      (node (ref "D24") (pin "C") (pinfunction "C_C") (pintype "passive"))
      (node (ref "D30") (pin "C") (pinfunction "C_C") (pintype "passive"))
      (node (ref "D36") (pin "C") (pinfunction "C_C") (pintype "passive"))
      (node (ref "D42") (pin "C") (pinfunction "C_C") (pintype "passive"))
      (node (ref "D48") (pin "C") (pinfunction "C_C") (pintype "passive"))
      (node (ref "D54") (pin "C") (pinfunction "C_C") (pintype "passive"))
      (node (ref "D57") (pin "C") (pinfunction "C_C") (pintype "passive"))
      (node (ref "D58") (pin "A") (pinfunction "A_A") (pintype "passive"))
      (node (ref "D6") (pin "C") (pinfunction "C_C") (pintype "passive"))
    )
    (net (code "85") (name "V-") (class "Default")
      (node (ref "D11") (pin "A") (pinfunction "A_A") (pintype "passive"))
      (node (ref "D17") (pin "A") (pinfunction "A_A") (pintype "passive"))
      (node (ref "D23") (pin "A") (pinfunction "A_A") (pintype "passive"))
      (node (ref "D29") (pin "A") (pinfunction "A_A") (pintype "passive"))
      (node (ref "D35") (pin "A") (pinfunction "A_A") (pintype "passive"))
      (node (ref "D41") (pin "A") (pinfunction "A_A") (pintype "passive"))
      (node (ref "D47") (pin "A") (pinfunction "A_A") (pintype "passive"))
      (node (ref "D5") (pin "A") (pinfunction "A_A") (pintype "passive"))
      (node (ref "D53") (pin "A") (pinfunction "A_A") (pintype "passive"))
      (node (ref "D65") (pin "C") (pinfunction "C_C") (pintype "passive"))
      (node (ref "R2") (pin "2") (pinfunction "2_2") (pintype "passive"))
    )
    (net (code "86") (name "VCC") (class "Default")
      (node (ref "C1") (pin "1") (pinfunction "1_1") (pintype "passive"))
      (node (ref "C2") (pin "1") (pinfunction "1_1") (pintype "passive"))
      (node (ref "D55") (pin "A") (pinfunction "A_A") (pintype "passive"))
      (node (ref "R1") (pin "1") (pinfunction "1_1") (pintype "passive"))
    )
    (net (code "87") (name "unconnected-(POSIBUS-Pad19)") (class "Default")
      (node (ref "POSIBUS") (pin "19") (pinfunction "19_19") (pintype "passive"))
    )
    (net (code "88") (name "unconnected-(U1A-A4-Pad8)") (class "Default")
      (node (ref "U1") (pin "8") (pinfunction "A4_8") (pintype "input"))
    )
    (net (code "89") (name "unconnected-(U1A-Y4-Pad12)") (class "Default")
      (node (ref "U1") (pin "12") (pinfunction "Y4_12") (pintype "tri_state"))
    )
    (net (code "90") (name "unconnected-(U2A-A4-Pad8)") (class "Default")
      (node (ref "U2") (pin "8") (pinfunction "A4_8") (pintype "input"))
    )
    (net (code "91") (name "unconnected-(U2A-Y4-Pad12)") (class "Default")
      (node (ref "U2") (pin "12") (pinfunction "Y4_12") (pintype "tri_state"))
    )
    (net (code "92") (name "unconnected-(U2B-A4-Pad17)") (class "Default")
      (node (ref "U2") (pin "17") (pinfunction "A4_17") (pintype "input"))
    )
    (net (code "93") (name "unconnected-(U2B-Y4-Pad3)") (class "Default")
      (node (ref "U2") (pin "3") (pinfunction "Y4_3") (pintype "tri_state"))
    )
  )
)
